# ft232-breakout.net
KiCad netlist of a schematic drawn in EAGLE
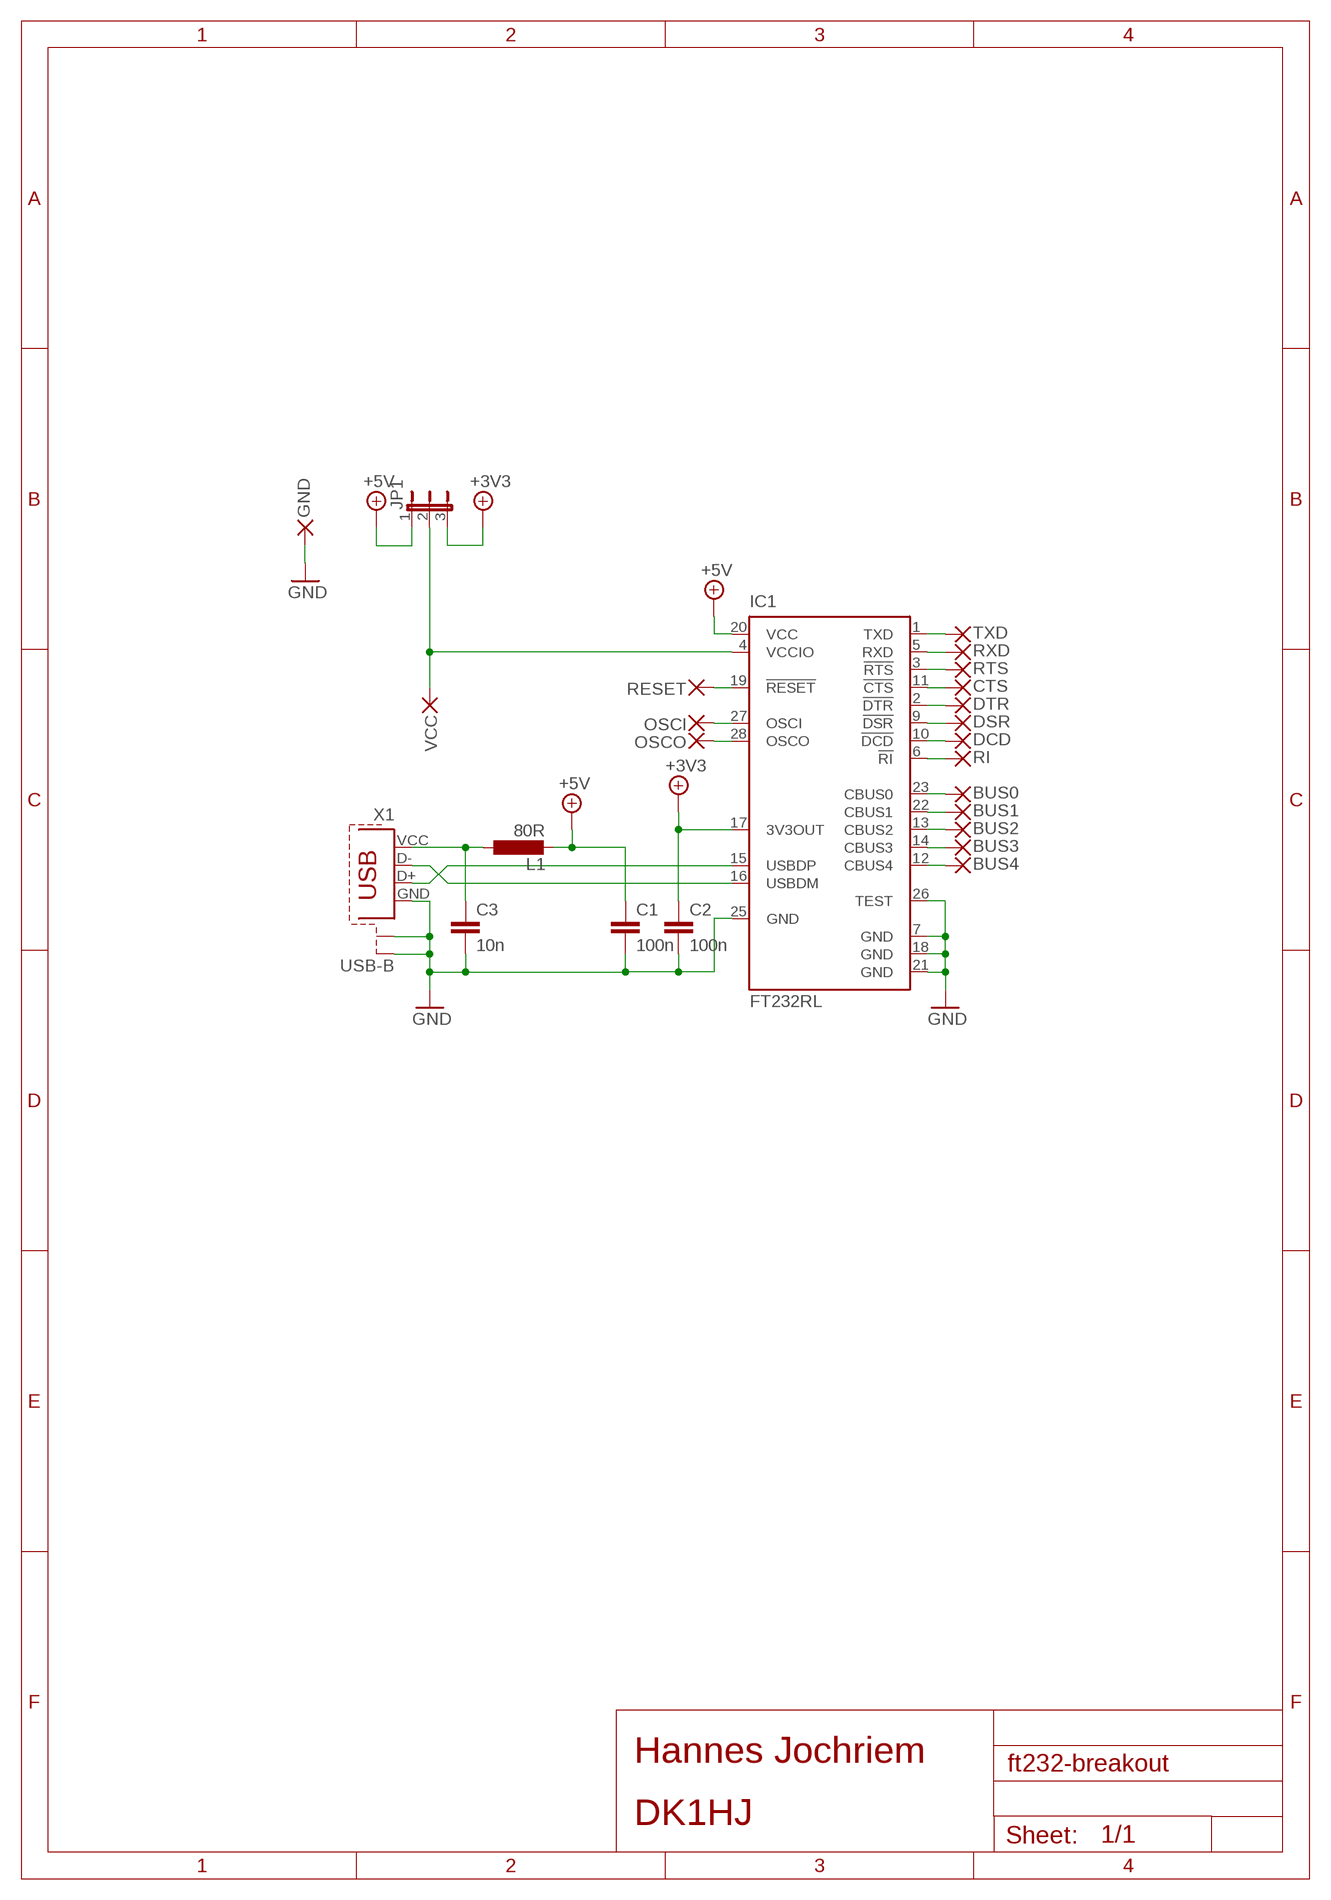
[diagram p0: schematic, sheet 1]

(export (version "E")
  (design (tool "Eeschema 10.0.6"))
  (components
    (comp (ref "BUS0")
      (value "WIREPAD2,15/1,0")
      (footprint "eagle-import:2,15_1,0")
      (libsource (lib "eagle-import") (part "WIREPAD2,15/1,0"))
    )
    (comp (ref "BUS1")
      (value "WIREPAD2,15/1,0")
      (footprint "eagle-import:2,15_1,0")
      (libsource (lib "eagle-import") (part "WIREPAD2,15/1,0"))
    )
    (comp (ref "BUS2")
      (value "WIREPAD2,15/1,0")
      (footprint "eagle-import:2,15_1,0")
      (libsource (lib "eagle-import") (part "WIREPAD2,15/1,0"))
    )
    (comp (ref "BUS3")
      (value "WIREPAD2,15/1,0")
      (footprint "eagle-import:2,15_1,0")
      (libsource (lib "eagle-import") (part "WIREPAD2,15/1,0"))
    )
    (comp (ref "BUS4")
      (value "WIREPAD2,15/1,0")
      (footprint "eagle-import:2,15_1,0")
      (libsource (lib "eagle-import") (part "WIREPAD2,15/1,0"))
    )
    (comp (ref "C1")
      (value "100n")
      (footprint "eagle-import:C0805")
      (libsource (lib "eagle-import") (part "CC0805"))
    )
    (comp (ref "C2")
      (value "100n")
      (footprint "eagle-import:C0805")
      (libsource (lib "eagle-import") (part "CC0805"))
    )
    (comp (ref "C3")
      (value "10n")
      (footprint "eagle-import:C0805")
      (libsource (lib "eagle-import") (part "CC0805"))
    )
    (comp (ref "CTS")
      (value "WIREPAD2,15/1,0")
      (footprint "eagle-import:2,15_1,0")
      (libsource (lib "eagle-import") (part "WIREPAD2,15/1,0"))
    )
    (comp (ref "DCD")
      (value "WIREPAD2,15/1,0")
      (footprint "eagle-import:2,15_1,0")
      (libsource (lib "eagle-import") (part "WIREPAD2,15/1,0"))
    )
    (comp (ref "DSR")
      (value "WIREPAD2,15/1,0")
      (footprint "eagle-import:2,15_1,0")
      (libsource (lib "eagle-import") (part "WIREPAD2,15/1,0"))
    )
    (comp (ref "DTR")
      (value "WIREPAD2,15/1,0")
      (footprint "eagle-import:2,15_1,0")
      (libsource (lib "eagle-import") (part "WIREPAD2,15/1,0"))
    )
    (comp (ref "GND")
      (value "WIREPAD2,15/1,0")
      (footprint "eagle-import:2,15_1,0")
      (libsource (lib "eagle-import") (part "WIREPAD2,15/1,0"))
    )
    (comp (ref "IC1")
      (value "FT232RL")
      (footprint "eagle-import:SSOP28")
      (libsource (lib "eagle-import") (part "FT232RL"))
    )
    (comp (ref "JP1")
      (value "JP2E")
      (footprint "eagle-import:JP2")
      (libsource (lib "eagle-import") (part "JP2E"))
    )
    (comp (ref "L1")
      (value "80R")
      (footprint "eagle-import:L2012C")
      (libsource (lib "eagle-import") (part "LL2012C"))
    )
    (comp (ref "OSCI")
      (value "WIREPAD2,15/1,0")
      (footprint "eagle-import:2,15_1,0")
      (libsource (lib "eagle-import") (part "WIREPAD2,15/1,0"))
    )
    (comp (ref "OSCO")
      (value "WIREPAD2,15/1,0")
      (footprint "eagle-import:2,15_1,0")
      (libsource (lib "eagle-import") (part "WIREPAD2,15/1,0"))
    )
    (comp (ref "RESET")
      (value "WIREPAD2,15/1,0")
      (footprint "eagle-import:2,15_1,0")
      (libsource (lib "eagle-import") (part "WIREPAD2,15/1,0"))
    )
    (comp (ref "RI")
      (value "WIREPAD2,15/1,0")
      (footprint "eagle-import:2,15_1,0")
      (libsource (lib "eagle-import") (part "WIREPAD2,15/1,0"))
    )
    (comp (ref "RTS")
      (value "WIREPAD2,15/1,0")
      (footprint "eagle-import:2,15_1,0")
      (libsource (lib "eagle-import") (part "WIREPAD2,15/1,0"))
    )
    (comp (ref "RXD")
      (value "WIREPAD2,15/1,0")
      (footprint "eagle-import:2,15_1,0")
      (libsource (lib "eagle-import") (part "WIREPAD2,15/1,0"))
    )
    (comp (ref "TXD")
      (value "WIREPAD2,15/1,0")
      (footprint "eagle-import:2,15_1,0")
      (libsource (lib "eagle-import") (part "WIREPAD2,15/1,0"))
    )
    (comp (ref "VCC")
      (value "WIREPAD2,15/1,0")
      (footprint "eagle-import:2,15_1,0")
      (libsource (lib "eagle-import") (part "WIREPAD2,15/1,0"))
    )
    (comp (ref "X1")
      (value "USB-B")
      (footprint "eagle-import:PN61729-S")
      (libsource (lib "eagle-import") (part "USB-B"))
    )
  )
  (nets
    (net (code "1") (name "+3V3") (class "Default")
      (node (ref "C2") (pin "1") (pinfunction "1_1") (pintype "passive"))
      (node (ref "IC1") (pin "17") (pinfunction "3V3OUT_17") (pintype "output"))
      (node (ref "JP1") (pin "3") (pinfunction "3_3") (pintype "passive"))
    )
    (net (code "2") (name "+5V") (class "Default")
      (node (ref "C1") (pin "1") (pinfunction "1_1") (pintype "passive"))
      (node (ref "IC1") (pin "20") (pinfunction "VCC_20") (pintype "power_in"))
      (node (ref "JP1") (pin "1") (pinfunction "1_1") (pintype "passive"))
      (node (ref "L1") (pin "2") (pinfunction "2_2") (pintype "passive"))
    )
    (net (code "3") (name "GND") (class "Default")
      (node (ref "C1") (pin "2") (pinfunction "2_2") (pintype "passive"))
      (node (ref "C2") (pin "2") (pinfunction "2_2") (pintype "passive"))
      (node (ref "C3") (pin "2") (pinfunction "2_2") (pintype "passive"))
      (node (ref "GND") (pin "1") (pinfunction "P_1") (pintype "passive"))
      (node (ref "IC1") (pin "18") (pinfunction "GND_18") (pintype "power_in"))
      (node (ref "IC1") (pin "21") (pinfunction "GND_21") (pintype "power_in"))
      (node (ref "IC1") (pin "25") (pinfunction "GND_25") (pintype "power_in"))
      (node (ref "IC1") (pin "26") (pinfunction "TEST_26") (pintype "input"))
      (node (ref "IC1") (pin "7") (pinfunction "GND_7") (pintype "power_in"))
      (node (ref "X1") (pin "GND") (pinfunction "GND_GND") (pintype "passive"))
      (node (ref "X1") (pin "S1") (pinfunction "S1_S1") (pintype "passive"))
      (node (ref "X1") (pin "S2") (pinfunction "S2_S2") (pintype "passive"))
    )
    (net (code "4") (name "Net-(BUS0-P)") (class "Default")
      (node (ref "BUS0") (pin "1") (pinfunction "P_1") (pintype "passive"))
      (node (ref "IC1") (pin "23") (pinfunction "CBUS0_23") (pintype "bidirectional"))
    )
    (net (code "5") (name "Net-(BUS1-P)") (class "Default")
      (node (ref "BUS1") (pin "1") (pinfunction "P_1") (pintype "passive"))
      (node (ref "IC1") (pin "22") (pinfunction "CBUS1_22") (pintype "bidirectional"))
    )
    (net (code "6") (name "Net-(BUS2-P)") (class "Default")
      (node (ref "BUS2") (pin "1") (pinfunction "P_1") (pintype "passive"))
      (node (ref "IC1") (pin "13") (pinfunction "CBUS2_13") (pintype "bidirectional"))
    )
    (net (code "7") (name "Net-(BUS3-P)") (class "Default")
      (node (ref "BUS3") (pin "1") (pinfunction "P_1") (pintype "passive"))
      (node (ref "IC1") (pin "14") (pinfunction "CBUS3_14") (pintype "bidirectional"))
    )
    (net (code "8") (name "Net-(BUS4-P)") (class "Default")
      (node (ref "BUS4") (pin "1") (pinfunction "P_1") (pintype "passive"))
      (node (ref "IC1") (pin "12") (pinfunction "CBUS4_12") (pintype "bidirectional"))
    )
    (net (code "9") (name "Net-(C3-Pad1)") (class "Default")
      (node (ref "C3") (pin "1") (pinfunction "1_1") (pintype "passive"))
      (node (ref "L1") (pin "1") (pinfunction "1_1") (pintype "passive"))
      (node (ref "X1") (pin "VCC") (pinfunction "VCC_VCC") (pintype "passive"))
    )
    (net (code "10") (name "Net-(CTS-P)") (class "Default")
      (node (ref "CTS") (pin "1") (pinfunction "P_1") (pintype "passive"))
      (node (ref "IC1") (pin "11") (pinfunction "~{CTS}_11") (pintype "input"))
    )
    (net (code "11") (name "Net-(DCD-P)") (class "Default")
      (node (ref "DCD") (pin "1") (pinfunction "P_1") (pintype "passive"))
      (node (ref "IC1") (pin "10") (pinfunction "~{DCD}_10") (pintype "input"))
    )
    (net (code "12") (name "Net-(DSR-P)") (class "Default")
      (node (ref "DSR") (pin "1") (pinfunction "P_1") (pintype "passive"))
      (node (ref "IC1") (pin "9") (pinfunction "~{DSR}_9") (pintype "input"))
    )
    (net (code "13") (name "Net-(DTR-P)") (class "Default")
      (node (ref "DTR") (pin "1") (pinfunction "P_1") (pintype "passive"))
      (node (ref "IC1") (pin "2") (pinfunction "~{DTR}_2") (pintype "output"))
    )
    (net (code "14") (name "Net-(IC1-OSCI)") (class "Default")
      (node (ref "IC1") (pin "27") (pinfunction "OSCI_27") (pintype "input"))
      (node (ref "OSCI") (pin "1") (pinfunction "P_1") (pintype "passive"))
    )
    (net (code "15") (name "Net-(IC1-OSCO)") (class "Default")
      (node (ref "IC1") (pin "28") (pinfunction "OSCO_28") (pintype "output"))
      (node (ref "OSCO") (pin "1") (pinfunction "P_1") (pintype "passive"))
    )
    (net (code "16") (name "Net-(IC1-RXD)") (class "Default")
      (node (ref "IC1") (pin "5") (pinfunction "RXD_5") (pintype "input"))
      (node (ref "RXD") (pin "1") (pinfunction "P_1") (pintype "passive"))
    )
    (net (code "17") (name "Net-(IC1-TXD)") (class "Default")
      (node (ref "IC1") (pin "1") (pinfunction "TXD_1") (pintype "output"))
      (node (ref "TXD") (pin "1") (pinfunction "P_1") (pintype "passive"))
    )
    (net (code "18") (name "Net-(IC1-USBDM)") (class "Default")
      (node (ref "IC1") (pin "16") (pinfunction "USBDM_16") (pintype "bidirectional"))
      (node (ref "X1") (pin "D-") (pinfunction "D-_D-") (pintype "passive"))
    )
    (net (code "19") (name "Net-(IC1-USBDP)") (class "Default")
      (node (ref "IC1") (pin "15") (pinfunction "USBDP_15") (pintype "bidirectional"))
      (node (ref "X1") (pin "D+") (pinfunction "D+_D+") (pintype "passive"))
    )
    (net (code "20") (name "Net-(IC1-VCCIO)") (class "Default")
      (node (ref "IC1") (pin "4") (pinfunction "VCCIO_4") (pintype "power_in"))
      (node (ref "JP1") (pin "2") (pinfunction "2_2") (pintype "passive"))
      (node (ref "VCC") (pin "1") (pinfunction "P_1") (pintype "passive"))
    )
    (net (code "21") (name "Net-(IC1-~{RESET})") (class "Default")
      (node (ref "IC1") (pin "19") (pinfunction "~{RESET}_19") (pintype "input"))
      (node (ref "RESET") (pin "1") (pinfunction "P_1") (pintype "passive"))
    )
    (net (code "22") (name "Net-(IC1-~{RI})") (class "Default")
      (node (ref "IC1") (pin "6") (pinfunction "~{RI}_6") (pintype "input"))
      (node (ref "RI") (pin "1") (pinfunction "P_1") (pintype "passive"))
    )
    (net (code "23") (name "Net-(IC1-~{RTS})") (class "Default")
      (node (ref "IC1") (pin "3") (pinfunction "~{RTS}_3") (pintype "output"))
      (node (ref "RTS") (pin "1") (pinfunction "P_1") (pintype "passive"))
    )
  )
)
